# miniKame.net
KiCad netlist of a schematic drawn in EAGLE
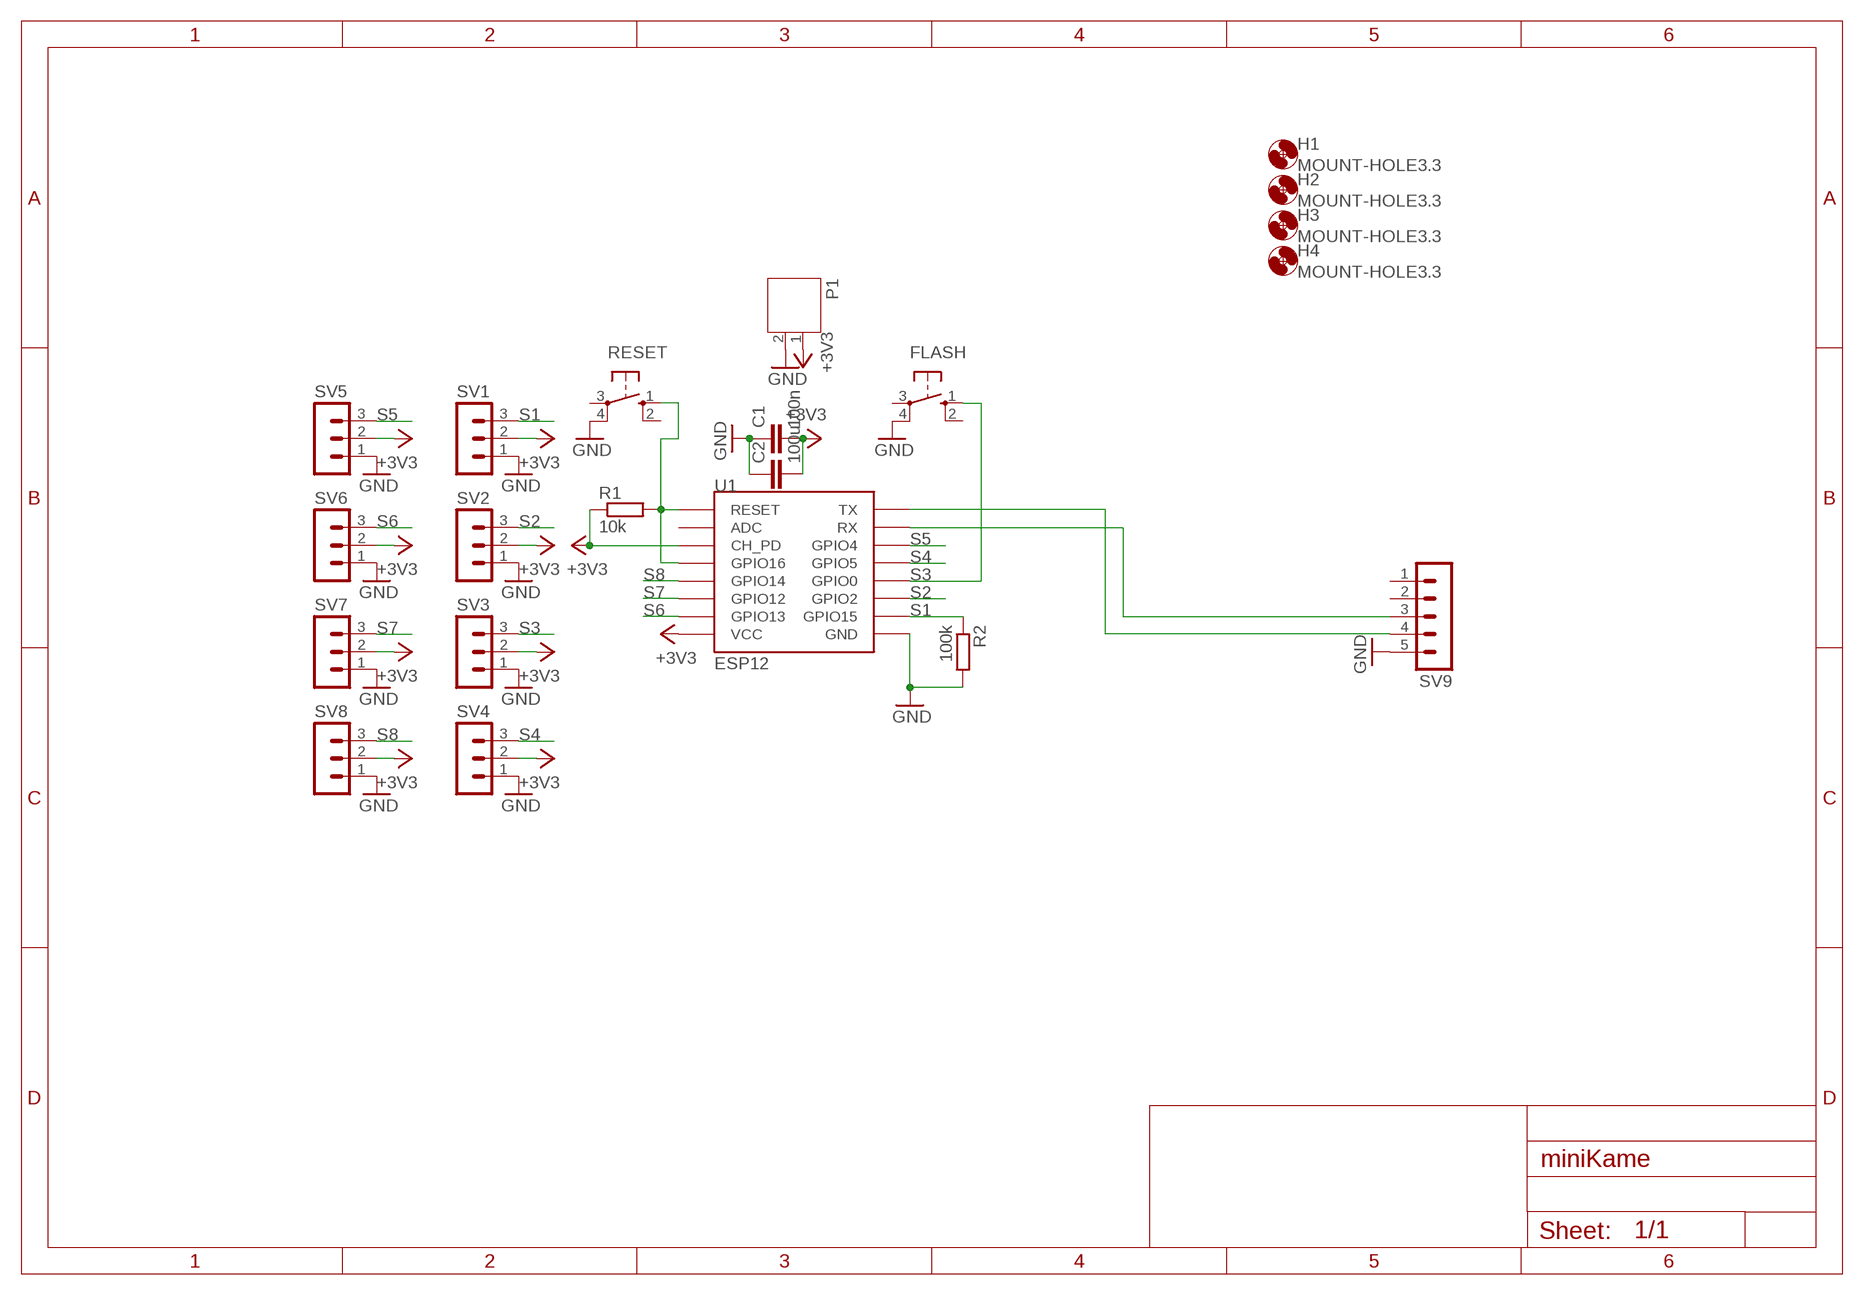
[diagram p0: schematic, sheet 1]

(export (version "E")
  (design (tool "Eeschema 10.0.6"))
  (components
    (comp (ref "C1")
      (value "100n")
      (footprint "eagle-import:C0805")
      (libsource (lib "eagle-import") (part "C-EUC0805"))
    )
    (comp (ref "C2")
      (value "100u")
      (footprint "eagle-import:C0805")
      (libsource (lib "eagle-import") (part "C-EUC0805"))
    )
    (comp (ref "FLASH")
      (value "10-XX")
      (footprint "eagle-import:B3F-10XX")
      (fields (field (name "MPN") "B3F-1000"))
      (libsource (lib "eagle-import") (part "10-XX"))
    )
    (comp (ref "H1")
      (value "MOUNT-HOLE3.3")
      (footprint "eagle-import:3,3")
      (libsource (lib "eagle-import") (part "MOUNT-HOLE3.3"))
    )
    (comp (ref "H2")
      (value "MOUNT-HOLE3.3")
      (footprint "eagle-import:3,3")
      (libsource (lib "eagle-import") (part "MOUNT-HOLE3.3"))
    )
    (comp (ref "H3")
      (value "MOUNT-HOLE3.3")
      (footprint "eagle-import:3,3")
      (libsource (lib "eagle-import") (part "MOUNT-HOLE3.3"))
    )
    (comp (ref "H4")
      (value "MOUNT-HOLE3.3")
      (footprint "eagle-import:3,3")
      (libsource (lib "eagle-import") (part "MOUNT-HOLE3.3"))
    )
    (comp (ref "P1")
      (value "JST-PH2")
      (footprint "eagle-import:JST-PH2")
      (libsource (lib "eagle-import") (part "JST-PH2"))
    )
    (comp (ref "R1")
      (value "10k")
      (footprint "eagle-import:M0805")
      (libsource (lib "eagle-import") (part "R-EU_M0805"))
    )
    (comp (ref "R2")
      (value "100k")
      (footprint "eagle-import:M0805")
      (libsource (lib "eagle-import") (part "R-EU_M0805"))
    )
    (comp (ref "RESET")
      (value "10-XX")
      (footprint "eagle-import:B3F-10XX")
      (fields (field (name "MPN") "B3F-1000"))
      (libsource (lib "eagle-import") (part "10-XX"))
    )
    (comp (ref "SV1")
      (value "MA03-1")
      (footprint "eagle-import:MA03-1")
      (libsource (lib "eagle-import") (part "MA03-1"))
    )
    (comp (ref "SV2")
      (value "MA03-1")
      (footprint "eagle-import:MA03-1")
      (libsource (lib "eagle-import") (part "MA03-1"))
    )
    (comp (ref "SV3")
      (value "MA03-1")
      (footprint "eagle-import:MA03-1")
      (libsource (lib "eagle-import") (part "MA03-1"))
    )
    (comp (ref "SV4")
      (value "MA03-1")
      (footprint "eagle-import:MA03-1")
      (libsource (lib "eagle-import") (part "MA03-1"))
    )
    (comp (ref "SV5")
      (value "MA03-1")
      (footprint "eagle-import:MA03-1")
      (libsource (lib "eagle-import") (part "MA03-1"))
    )
    (comp (ref "SV6")
      (value "MA03-1")
      (footprint "eagle-import:MA03-1")
      (libsource (lib "eagle-import") (part "MA03-1"))
    )
    (comp (ref "SV7")
      (value "MA03-1")
      (footprint "eagle-import:MA03-1")
      (libsource (lib "eagle-import") (part "MA03-1"))
    )
    (comp (ref "SV8")
      (value "MA03-1")
      (footprint "eagle-import:MA03-1")
      (libsource (lib "eagle-import") (part "MA03-1"))
    )
    (comp (ref "SV9")
      (value "MA05-1")
      (footprint "eagle-import:MA05-1")
      (libsource (lib "eagle-import") (part "MA05-1"))
    )
    (comp (ref "U1")
      (value "ESP12")
      (footprint "eagle-import:ESP12")
      (libsource (lib "eagle-import") (part "ESP12"))
    )
  )
  (nets
    (net (code "1") (name "+3V3") (class "Default")
      (node (ref "C1") (pin "2") (pinfunction "2_2") (pintype "passive"))
      (node (ref "C2") (pin "2") (pinfunction "2_2") (pintype "passive"))
      (node (ref "P1") (pin "1") (pinfunction "1_1") (pintype "passive"))
      (node (ref "R1") (pin "1") (pinfunction "1_1") (pintype "passive"))
      (node (ref "SV1") (pin "2") (pinfunction "2_2") (pintype "passive"))
      (node (ref "SV2") (pin "2") (pinfunction "2_2") (pintype "passive"))
      (node (ref "SV3") (pin "2") (pinfunction "2_2") (pintype "passive"))
      (node (ref "SV4") (pin "2") (pinfunction "2_2") (pintype "passive"))
      (node (ref "SV5") (pin "2") (pinfunction "2_2") (pintype "passive"))
      (node (ref "SV6") (pin "2") (pinfunction "2_2") (pintype "passive"))
      (node (ref "SV7") (pin "2") (pinfunction "2_2") (pintype "passive"))
      (node (ref "SV8") (pin "2") (pinfunction "2_2") (pintype "passive"))
      (node (ref "U1") (pin "CH_PD") (pinfunction "CH_PD_CH_PD") (pintype "bidirectional"))
      (node (ref "U1") (pin "VCC") (pinfunction "VCC_VCC") (pintype "bidirectional"))
    )
    (net (code "2") (name "/S1") (class "Default")
      (node (ref "R2") (pin "1") (pinfunction "1_1") (pintype "passive"))
      (node (ref "SV1") (pin "3") (pinfunction "3_3") (pintype "passive"))
      (node (ref "U1") (pin "GPIO15") (pinfunction "GPIO15_GPIO15") (pintype "bidirectional"))
    )
    (net (code "3") (name "/S2") (class "Default")
      (node (ref "SV2") (pin "3") (pinfunction "3_3") (pintype "passive"))
      (node (ref "U1") (pin "GPIO2") (pinfunction "GPIO2_GPIO2") (pintype "bidirectional"))
    )
    (net (code "4") (name "/S3") (class "Default")
      (node (ref "FLASH") (pin "1") (pinfunction "S_1") (pintype "passive"))
      (node (ref "SV3") (pin "3") (pinfunction "3_3") (pintype "passive"))
      (node (ref "U1") (pin "GPIO0") (pinfunction "GPIO0_GPIO0") (pintype "bidirectional"))
    )
    (net (code "5") (name "/S4") (class "Default")
      (node (ref "SV4") (pin "3") (pinfunction "3_3") (pintype "passive"))
      (node (ref "U1") (pin "GPIO5") (pinfunction "GPIO5_GPIO5") (pintype "bidirectional"))
    )
    (net (code "6") (name "/S5") (class "Default")
      (node (ref "SV5") (pin "3") (pinfunction "3_3") (pintype "passive"))
      (node (ref "U1") (pin "GPIO4") (pinfunction "GPIO4_GPIO4") (pintype "bidirectional"))
    )
    (net (code "7") (name "/S6") (class "Default")
      (node (ref "SV6") (pin "3") (pinfunction "3_3") (pintype "passive"))
      (node (ref "U1") (pin "GPIO13") (pinfunction "GPIO13_GPIO13") (pintype "bidirectional"))
    )
    (net (code "8") (name "/S7") (class "Default")
      (node (ref "SV7") (pin "3") (pinfunction "3_3") (pintype "passive"))
      (node (ref "U1") (pin "GPIO12") (pinfunction "GPIO12_GPIO12") (pintype "bidirectional"))
    )
    (net (code "9") (name "/S8") (class "Default")
      (node (ref "SV8") (pin "3") (pinfunction "3_3") (pintype "passive"))
      (node (ref "U1") (pin "GPIO14") (pinfunction "GPIO14_GPIO14") (pintype "bidirectional"))
    )
    (net (code "10") (name "GND") (class "Default")
      (node (ref "C1") (pin "1") (pinfunction "1_1") (pintype "passive"))
      (node (ref "C2") (pin "1") (pinfunction "1_1") (pintype "passive"))
      (node (ref "FLASH") (pin "4") (pinfunction "P1_4") (pintype "passive"))
      (node (ref "P1") (pin "2") (pinfunction "2_2") (pintype "passive"))
      (node (ref "R2") (pin "2") (pinfunction "2_2") (pintype "passive"))
      (node (ref "RESET") (pin "4") (pinfunction "P1_4") (pintype "passive"))
      (node (ref "SV1") (pin "1") (pinfunction "1_1") (pintype "passive"))
      (node (ref "SV2") (pin "1") (pinfunction "1_1") (pintype "passive"))
      (node (ref "SV3") (pin "1") (pinfunction "1_1") (pintype "passive"))
      (node (ref "SV4") (pin "1") (pinfunction "1_1") (pintype "passive"))
      (node (ref "SV5") (pin "1") (pinfunction "1_1") (pintype "passive"))
      (node (ref "SV6") (pin "1") (pinfunction "1_1") (pintype "passive"))
      (node (ref "SV7") (pin "1") (pinfunction "1_1") (pintype "passive"))
      (node (ref "SV8") (pin "1") (pinfunction "1_1") (pintype "passive"))
      (node (ref "SV9") (pin "5") (pinfunction "5_5") (pintype "passive"))
      (node (ref "U1") (pin "GND") (pinfunction "GND_GND") (pintype "bidirectional"))
    )
    (net (code "11") (name "Net-(RESET-S)") (class "Default")
      (node (ref "R1") (pin "2") (pinfunction "2_2") (pintype "passive"))
      (node (ref "RESET") (pin "1") (pinfunction "S_1") (pintype "passive"))
      (node (ref "U1") (pin "GPIO16") (pinfunction "GPIO16_GPIO16") (pintype "bidirectional"))
      (node (ref "U1") (pin "RESET") (pinfunction "RESET_RESET") (pintype "bidirectional"))
    )
    (net (code "12") (name "Net-(SV9-Pad3)") (class "Default")
      (node (ref "SV9") (pin "3") (pinfunction "3_3") (pintype "passive"))
      (node (ref "U1") (pin "RX") (pinfunction "RX_RX") (pintype "bidirectional"))
    )
    (net (code "13") (name "Net-(SV9-Pad4)") (class "Default")
      (node (ref "SV9") (pin "4") (pinfunction "4_4") (pintype "passive"))
      (node (ref "U1") (pin "TX") (pinfunction "TX_TX") (pintype "bidirectional"))
    )
    (net (code "14") (name "unconnected-(FLASH-P-Pad3)") (class "Default")
      (node (ref "FLASH") (pin "3") (pinfunction "P_3") (pintype "passive"))
    )
    (net (code "15") (name "unconnected-(FLASH-S1-Pad2)") (class "Default")
      (node (ref "FLASH") (pin "2") (pinfunction "S1_2") (pintype "passive"))
    )
    (net (code "16") (name "unconnected-(RESET-P-Pad3)") (class "Default")
      (node (ref "RESET") (pin "3") (pinfunction "P_3") (pintype "passive"))
    )
    (net (code "17") (name "unconnected-(RESET-S1-Pad2)") (class "Default")
      (node (ref "RESET") (pin "2") (pinfunction "S1_2") (pintype "passive"))
    )
    (net (code "18") (name "unconnected-(SV9-Pad1)") (class "Default")
      (node (ref "SV9") (pin "1") (pinfunction "1_1") (pintype "passive"))
    )
    (net (code "19") (name "unconnected-(SV9-Pad2)") (class "Default")
      (node (ref "SV9") (pin "2") (pinfunction "2_2") (pintype "passive"))
    )
    (net (code "20") (name "unconnected-(U1-PadADC)") (class "Default")
      (node (ref "U1") (pin "ADC") (pinfunction "ADC_ADC") (pintype "bidirectional"))
    )
  )
)
